# HSDACircuit.net
KiCad netlist of a schematic drawn in Altium Designer
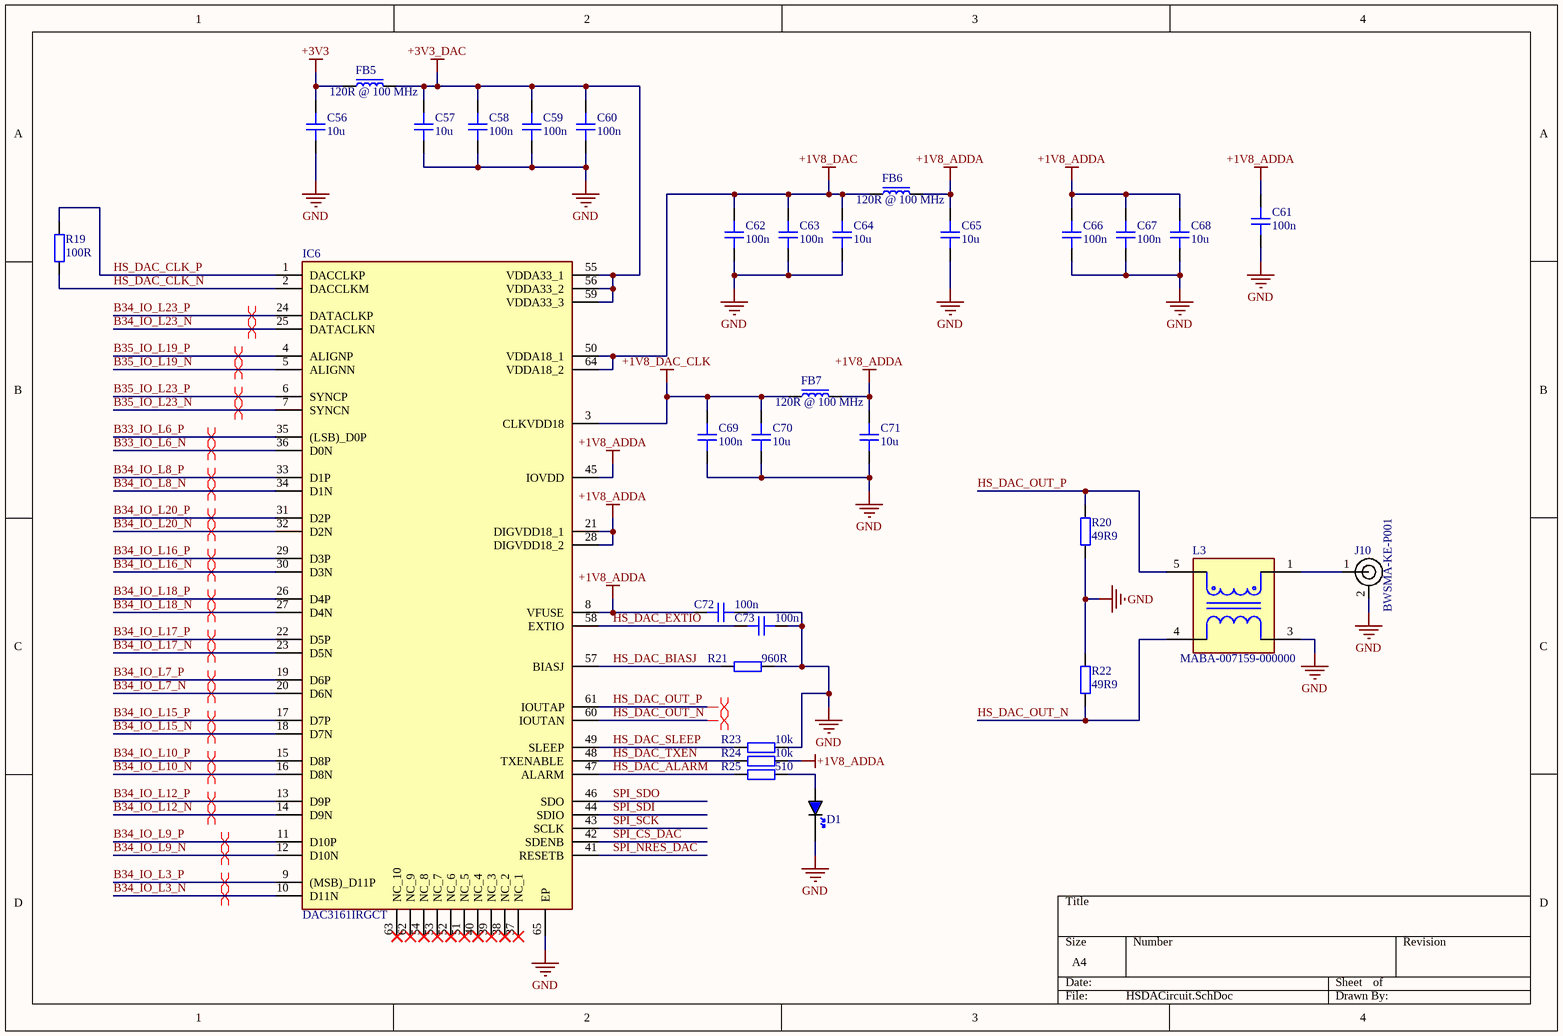
[diagram p0: HSDACircuit.SchDoc]

(export (version "E")
  (design (tool "Eeschema 10.0.6"))
  (components
    (comp (ref "C56")
      (value "10u")
      (footprint "CAP_0603")
      (description "Capacitor SMD 0603")
      (libsource (lib "Schematic-Lib-PhilsLab") (part "CAP_0603"))
    )
    (comp (ref "C57")
      (value "10u")
      (footprint "CAP_0603")
      (description "Capacitor SMD 0603")
      (libsource (lib "Schematic-Lib-PhilsLab") (part "CAP_0603"))
    )
    (comp (ref "C58")
      (value "100n")
      (footprint "CAP_0402")
      (description "Capacitor SMD 0402")
      (libsource (lib "Schematic-Lib-PhilsLab") (part "CAP_0402"))
    )
    (comp (ref "C59")
      (value "100n")
      (footprint "CAP_0402")
      (description "Capacitor SMD 0402")
      (libsource (lib "Schematic-Lib-PhilsLab") (part "CAP_0402"))
    )
    (comp (ref "C60")
      (value "100n")
      (footprint "CAP_0402")
      (description "Capacitor SMD 0402")
      (libsource (lib "Schematic-Lib-PhilsLab") (part "CAP_0402"))
    )
    (comp (ref "C61")
      (value "100n")
      (footprint "CAP_0402")
      (description "Capacitor SMD 0402")
      (libsource (lib "Schematic-Lib-PhilsLab") (part "CAP_0402"))
    )
    (comp (ref "C62")
      (value "100n")
      (footprint "CAP_0402")
      (description "Capacitor SMD 0402")
      (libsource (lib "Schematic-Lib-PhilsLab") (part "CAP_0402"))
    )
    (comp (ref "C63")
      (value "100n")
      (footprint "CAP_0402")
      (description "Capacitor SMD 0402")
      (libsource (lib "Schematic-Lib-PhilsLab") (part "CAP_0402"))
    )
    (comp (ref "C64")
      (value "10u")
      (footprint "CAP_0603")
      (description "Capacitor SMD 0603")
      (libsource (lib "Schematic-Lib-PhilsLab") (part "CAP_0603"))
    )
    (comp (ref "C65")
      (value "10u")
      (footprint "CAP_0603")
      (description "Capacitor SMD 0603")
      (libsource (lib "Schematic-Lib-PhilsLab") (part "CAP_0603"))
    )
    (comp (ref "C66")
      (value "100n")
      (footprint "CAP_0402")
      (description "Capacitor SMD 0402")
      (libsource (lib "Schematic-Lib-PhilsLab") (part "CAP_0402"))
    )
    (comp (ref "C67")
      (value "100n")
      (footprint "CAP_0402")
      (description "Capacitor SMD 0402")
      (libsource (lib "Schematic-Lib-PhilsLab") (part "CAP_0402"))
    )
    (comp (ref "C68")
      (value "10u")
      (footprint "CAP_0603")
      (description "Capacitor SMD 0603")
      (libsource (lib "Schematic-Lib-PhilsLab") (part "CAP_0603"))
    )
    (comp (ref "C69")
      (value "100n")
      (footprint "CAP_0402")
      (description "Capacitor SMD 0402")
      (libsource (lib "Schematic-Lib-PhilsLab") (part "CAP_0402"))
    )
    (comp (ref "C70")
      (value "10u")
      (footprint "CAP_0603")
      (description "Capacitor SMD 0603")
      (libsource (lib "Schematic-Lib-PhilsLab") (part "CAP_0603"))
    )
    (comp (ref "C71")
      (value "10u")
      (footprint "CAP_0603")
      (description "Capacitor SMD 0603")
      (libsource (lib "Schematic-Lib-PhilsLab") (part "CAP_0603"))
    )
    (comp (ref "C72")
      (value "100n")
      (footprint "CAP_0402")
      (description "Capacitor SMD 0402")
      (libsource (lib "Schematic-Lib-PhilsLab") (part "CAP_0402"))
    )
    (comp (ref "C73")
      (value "100n")
      (footprint "CAP_0402")
      (description "Capacitor SMD 0402")
      (libsource (lib "Schematic-Lib-PhilsLab") (part "CAP_0402"))
    )
    (comp (ref "D1")
      (value "BLUE")
      (footprint "LED_0603_BLUE")
      (description "LED 0603 BLUE SMD")
      (libsource (lib "Schematic-Lib-PhilsLab") (part "LED_0603_BLUE"))
    )
    (comp (ref "FB5")
      (value "120R @ 100 MHz")
      (footprint "FB_0603")
      (description "Ferrite Bead SMD 0603")
      (libsource (lib "") (part "FB_0603_1"))
    )
    (comp (ref "FB6")
      (value "120R @ 100 MHz")
      (footprint "FB_0603")
      (description "Ferrite Bead SMD 0603")
      (libsource (lib "Schematic-Lib-PhilsLab") (part "FB_0603"))
    )
    (comp (ref "FB7")
      (value "120R @ 100 MHz")
      (footprint "FB_0603")
      (description "Ferrite Bead SMD 0603")
      (libsource (lib "Schematic-Lib-PhilsLab") (part "FB_0603"))
    )
    (comp (ref "IC6")
      (value "DAC3161IRGCT")
      (footprint "JetsonTx2_PCBLib:QFN50P900X900X100-65N-D")
      (description "Integrated Circuit")
      (fields (field (name "MOUSER PART NUMBER") "595-DAC3161IRGCT"))
      (libsource (lib "JetsonTx2_SCHLib") (part "DAC3161IRGCT"))
    )
    (comp (ref "J10")
      (value "BWSMA-KE-P001")
      (footprint "BWSMA-KE-P001")
      (libsource (lib "JetsonTx2_SCHLib") (part "BWSMA-KE-P001"))
    )
    (comp (ref "L3")
      (value "MABA-007159-000000")
      (footprint "FP-MABA-007159-000000-MFG")
      (description "BALUN 4.5MHZ-3GHZ 1:1 6SMD FLAT")
      (libsource (lib "JetsonTx2_SCHLib") (part "MABA-007159-000000"))
    )
    (comp (ref "R19")
      (value "100R")
      (footprint "RES_0402")
      (description "Resistor SMD 0402")
      (libsource (lib "Schematic-Lib-PhilsLab") (part "RES_0402"))
    )
    (comp (ref "R20")
      (value "49R9")
      (footprint "RES_0402")
      (description "Resistor SMD 0402")
      (libsource (lib "Schematic-Lib-PhilsLab") (part "RES_0402"))
    )
    (comp (ref "R21")
      (value "960R")
      (footprint "RES_0402")
      (description "Resistor SMD 0402")
      (libsource (lib "Schematic-Lib-PhilsLab") (part "RES_0402"))
    )
    (comp (ref "R22")
      (value "49R9")
      (footprint "RES_0402")
      (description "Resistor SMD 0402")
      (libsource (lib "Schematic-Lib-PhilsLab") (part "RES_0402"))
    )
    (comp (ref "R23")
      (value "10k")
      (footprint "RES_0402")
      (description "Resistor SMD 0402")
      (libsource (lib "Schematic-Lib-PhilsLab") (part "RES_0402"))
    )
    (comp (ref "R24")
      (value "10k")
      (footprint "RES_0402")
      (description "Resistor SMD 0402")
      (libsource (lib "Schematic-Lib-PhilsLab") (part "RES_0402"))
    )
    (comp (ref "R25")
      (value "510")
      (footprint "RES_0603")
      (description "Resistor SMD 0603")
      (libsource (lib "Schematic-Lib-PhilsLab") (part "RES_0603"))
    )
  )
  (nets
    (net (code "1") (name "+1V8_ADDA") (class "Default")
      (node (ref "C61") (pin "1") (pinfunction "1_1") (pintype "passive"))
      (node (ref "C65") (pin "2") (pinfunction "2_2") (pintype "passive"))
      (node (ref "C66") (pin "1") (pinfunction "1_1") (pintype "passive"))
      (node (ref "C67") (pin "1") (pinfunction "1_1") (pintype "passive"))
      (node (ref "C68") (pin "2") (pinfunction "2_2") (pintype "passive"))
      (node (ref "C71") (pin "2") (pinfunction "2_2") (pintype "passive"))
      (node (ref "C72") (pin "1") (pinfunction "1_1") (pintype "passive"))
      (node (ref "FB6") (pin "2") (pinfunction "2_2") (pintype "passive"))
      (node (ref "FB7") (pin "2") (pinfunction "2_2") (pintype "passive"))
      (node (ref "IC6") (pin "21") (pinfunction "DIGVDD18_1_21") (pintype "passive"))
      (node (ref "IC6") (pin "28") (pinfunction "DIGVDD18_2_28") (pintype "passive"))
      (node (ref "IC6") (pin "45") (pinfunction "IOVDD_45") (pintype "passive"))
      (node (ref "IC6") (pin "8") (pinfunction "VFUSE_8") (pintype "passive"))
      (node (ref "R24") (pin "1") (pinfunction "1_1") (pintype "passive"))
    )
    (net (code "2") (name "+1V8_DAC") (class "Default")
      (node (ref "C62") (pin "1") (pinfunction "1_1") (pintype "passive"))
      (node (ref "C63") (pin "1") (pinfunction "1_1") (pintype "passive"))
      (node (ref "C64") (pin "2") (pinfunction "2_2") (pintype "passive"))
      (node (ref "FB6") (pin "1") (pinfunction "1_1") (pintype "passive"))
      (node (ref "IC6") (pin "50") (pinfunction "VDDA18_1_50") (pintype "passive"))
      (node (ref "IC6") (pin "64") (pinfunction "VDDA18_2_64") (pintype "passive"))
    )
    (net (code "3") (name "+1V8_DAC_CLK") (class "Default")
      (node (ref "C69") (pin "1") (pinfunction "1_1") (pintype "passive"))
      (node (ref "C70") (pin "2") (pinfunction "2_2") (pintype "passive"))
      (node (ref "FB7") (pin "1") (pinfunction "1_1") (pintype "passive"))
      (node (ref "IC6") (pin "3") (pinfunction "CLKVDD18_3") (pintype "passive"))
    )
    (net (code "4") (name "+3V3") (class "Default")
      (node (ref "C56") (pin "2") (pinfunction "2_2") (pintype "passive"))
      (node (ref "FB5") (pin "2") (pinfunction "2_2") (pintype "passive"))
    )
    (net (code "5") (name "+3V3_DAC") (class "Default")
      (node (ref "C57") (pin "2") (pinfunction "2_2") (pintype "passive"))
      (node (ref "C58") (pin "1") (pinfunction "1_1") (pintype "passive"))
      (node (ref "C59") (pin "1") (pinfunction "1_1") (pintype "passive"))
      (node (ref "C60") (pin "1") (pinfunction "1_1") (pintype "passive"))
      (node (ref "FB5") (pin "1") (pinfunction "1_1") (pintype "passive"))
      (node (ref "IC6") (pin "55") (pinfunction "VDDA33_1_55") (pintype "passive"))
      (node (ref "IC6") (pin "56") (pinfunction "VDDA33_2_56") (pintype "passive"))
      (node (ref "IC6") (pin "59") (pinfunction "VDDA33_3_59") (pintype "passive"))
    )
    (net (code "6") (name "/B33_IO_L6_N") (class "Default")
      (node (ref "IC6") (pin "36") (pinfunction "D0N_36") (pintype "passive"))
    )
    (net (code "7") (name "/B33_IO_L6_P") (class "Default")
      (node (ref "IC6") (pin "35") (pinfunction "(LSB)_D0P_35") (pintype "passive"))
    )
    (net (code "8") (name "/B34_IO_L3_N") (class "Default")
      (node (ref "IC6") (pin "10") (pinfunction "D11N_10") (pintype "passive"))
    )
    (net (code "9") (name "/B34_IO_L3_P") (class "Default")
      (node (ref "IC6") (pin "9") (pinfunction "(MSB)_D11P_9") (pintype "passive"))
    )
    (net (code "10") (name "/B34_IO_L7_N") (class "Default")
      (node (ref "IC6") (pin "20") (pinfunction "D6N_20") (pintype "passive"))
    )
    (net (code "11") (name "/B34_IO_L7_P") (class "Default")
      (node (ref "IC6") (pin "19") (pinfunction "D6P_19") (pintype "passive"))
    )
    (net (code "12") (name "/B34_IO_L8_N") (class "Default")
      (node (ref "IC6") (pin "34") (pinfunction "D1N_34") (pintype "passive"))
    )
    (net (code "13") (name "/B34_IO_L8_P") (class "Default")
      (node (ref "IC6") (pin "33") (pinfunction "D1P_33") (pintype "passive"))
    )
    (net (code "14") (name "/B34_IO_L9_N") (class "Default")
      (node (ref "IC6") (pin "12") (pinfunction "D10N_12") (pintype "passive"))
    )
    (net (code "15") (name "/B34_IO_L9_P") (class "Default")
      (node (ref "IC6") (pin "11") (pinfunction "D10P_11") (pintype "passive"))
    )
    (net (code "16") (name "/B34_IO_L10_N") (class "Default")
      (node (ref "IC6") (pin "16") (pinfunction "D8N_16") (pintype "passive"))
    )
    (net (code "17") (name "/B34_IO_L10_P") (class "Default")
      (node (ref "IC6") (pin "15") (pinfunction "D8P_15") (pintype "passive"))
    )
    (net (code "18") (name "/B34_IO_L12_N") (class "Default")
      (node (ref "IC6") (pin "14") (pinfunction "D9N_14") (pintype "passive"))
    )
    (net (code "19") (name "/B34_IO_L12_P") (class "Default")
      (node (ref "IC6") (pin "13") (pinfunction "D9P_13") (pintype "passive"))
    )
    (net (code "20") (name "/B34_IO_L15_N") (class "Default")
      (node (ref "IC6") (pin "18") (pinfunction "D7N_18") (pintype "passive"))
    )
    (net (code "21") (name "/B34_IO_L15_P") (class "Default")
      (node (ref "IC6") (pin "17") (pinfunction "D7P_17") (pintype "passive"))
    )
    (net (code "22") (name "/B34_IO_L16_N") (class "Default")
      (node (ref "IC6") (pin "30") (pinfunction "D3N_30") (pintype "passive"))
    )
    (net (code "23") (name "/B34_IO_L16_P") (class "Default")
      (node (ref "IC6") (pin "29") (pinfunction "D3P_29") (pintype "passive"))
    )
    (net (code "24") (name "/B34_IO_L17_N") (class "Default")
      (node (ref "IC6") (pin "23") (pinfunction "D5N_23") (pintype "passive"))
    )
    (net (code "25") (name "/B34_IO_L17_P") (class "Default")
      (node (ref "IC6") (pin "22") (pinfunction "D5P_22") (pintype "passive"))
    )
    (net (code "26") (name "/B34_IO_L18_N") (class "Default")
      (node (ref "IC6") (pin "27") (pinfunction "D4N_27") (pintype "passive"))
    )
    (net (code "27") (name "/B34_IO_L18_P") (class "Default")
      (node (ref "IC6") (pin "26") (pinfunction "D4P_26") (pintype "passive"))
    )
    (net (code "28") (name "/B34_IO_L20_N") (class "Default")
      (node (ref "IC6") (pin "32") (pinfunction "D2N_32") (pintype "passive"))
    )
    (net (code "29") (name "/B34_IO_L20_P") (class "Default")
      (node (ref "IC6") (pin "31") (pinfunction "D2P_31") (pintype "passive"))
    )
    (net (code "30") (name "/B34_IO_L23_N") (class "Default")
      (node (ref "IC6") (pin "25") (pinfunction "DATACLKN_25") (pintype "passive"))
    )
    (net (code "31") (name "/B34_IO_L23_P") (class "Default")
      (node (ref "IC6") (pin "24") (pinfunction "DATACLKP_24") (pintype "passive"))
    )
    (net (code "32") (name "/B35_IO_L19_N") (class "Default")
      (node (ref "IC6") (pin "5") (pinfunction "ALIGNN_5") (pintype "passive"))
    )
    (net (code "33") (name "/B35_IO_L19_P") (class "Default")
      (node (ref "IC6") (pin "4") (pinfunction "ALIGNP_4") (pintype "passive"))
    )
    (net (code "34") (name "/B35_IO_L23_N") (class "Default")
      (node (ref "IC6") (pin "7") (pinfunction "SYNCN_7") (pintype "passive"))
    )
    (net (code "35") (name "/B35_IO_L23_P") (class "Default")
      (node (ref "IC6") (pin "6") (pinfunction "SYNCP_6") (pintype "passive"))
    )
    (net (code "36") (name "/HS_DAC_ALARM") (class "Default")
      (node (ref "IC6") (pin "47") (pinfunction "ALARM_47") (pintype "passive"))
      (node (ref "R25") (pin "1") (pinfunction "1_1") (pintype "passive"))
    )
    (net (code "37") (name "/HS_DAC_BIASJ") (class "Default")
      (node (ref "IC6") (pin "57") (pinfunction "BIASJ_57") (pintype "passive"))
      (node (ref "R21") (pin "2") (pinfunction "2_2") (pintype "passive"))
    )
    (net (code "38") (name "/HS_DAC_CLK_N") (class "Default")
      (node (ref "IC6") (pin "2") (pinfunction "DACCLKM_2") (pintype "passive"))
      (node (ref "R19") (pin "1") (pinfunction "1_1") (pintype "passive"))
    )
    (net (code "39") (name "/HS_DAC_CLK_P") (class "Default")
      (node (ref "IC6") (pin "1") (pinfunction "DACCLKP_1") (pintype "passive"))
      (node (ref "R19") (pin "2") (pinfunction "2_2") (pintype "passive"))
    )
    (net (code "40") (name "/HS_DAC_EXTIO") (class "Default")
      (node (ref "C73") (pin "1") (pinfunction "1_1") (pintype "passive"))
      (node (ref "IC6") (pin "58") (pinfunction "EXTIO_58") (pintype "passive"))
    )
    (net (code "41") (name "/HS_DAC_OUT_N") (class "Default")
      (node (ref "IC6") (pin "60") (pinfunction "IOUTAN_60") (pintype "passive"))
      (node (ref "L3") (pin "4") (pinfunction "Primary_4") (pintype "passive"))
      (node (ref "R22") (pin "2") (pinfunction "2_2") (pintype "passive"))
    )
    (net (code "42") (name "/HS_DAC_OUT_P") (class "Default")
      (node (ref "IC6") (pin "61") (pinfunction "IOUTAP_61") (pintype "passive"))
      (node (ref "L3") (pin "5") (pinfunction "Primary_Dot_5") (pintype "passive"))
      (node (ref "R20") (pin "1") (pinfunction "1_1") (pintype "passive"))
    )
    (net (code "43") (name "/HS_DAC_SLEEP") (class "Default")
      (node (ref "IC6") (pin "49") (pinfunction "SLEEP_49") (pintype "passive"))
      (node (ref "R23") (pin "2") (pinfunction "2_2") (pintype "passive"))
    )
    (net (code "44") (name "/HS_DAC_TXEN") (class "Default")
      (node (ref "IC6") (pin "48") (pinfunction "TXENABLE_48") (pintype "passive"))
      (node (ref "R24") (pin "2") (pinfunction "2_2") (pintype "passive"))
    )
    (net (code "45") (name "/SPI_CS_DAC") (class "Default")
      (node (ref "IC6") (pin "42") (pinfunction "SDENB_42") (pintype "passive"))
    )
    (net (code "46") (name "/SPI_NRES_DAC") (class "Default")
      (node (ref "IC6") (pin "41") (pinfunction "RESETB_41") (pintype "passive"))
    )
    (net (code "47") (name "/SPI_SCK") (class "Default")
      (node (ref "IC6") (pin "43") (pinfunction "SCLK_43") (pintype "passive"))
    )
    (net (code "48") (name "/SPI_SDI") (class "Default")
      (node (ref "IC6") (pin "44") (pinfunction "SDIO_44") (pintype "passive"))
    )
    (net (code "49") (name "/SPI_SDO") (class "Default")
      (node (ref "IC6") (pin "46") (pinfunction "SDO_46") (pintype "passive"))
    )
    (net (code "50") (name "GND") (class "Default")
      (node (ref "C56") (pin "1") (pinfunction "1_1") (pintype "passive"))
      (node (ref "C57") (pin "1") (pinfunction "1_1") (pintype "passive"))
      (node (ref "C58") (pin "2") (pinfunction "2_2") (pintype "passive"))
      (node (ref "C59") (pin "2") (pinfunction "2_2") (pintype "passive"))
      (node (ref "C60") (pin "2") (pinfunction "2_2") (pintype "passive"))
      (node (ref "C61") (pin "2") (pinfunction "2_2") (pintype "passive"))
      (node (ref "C62") (pin "2") (pinfunction "2_2") (pintype "passive"))
      (node (ref "C63") (pin "2") (pinfunction "2_2") (pintype "passive"))
      (node (ref "C64") (pin "1") (pinfunction "1_1") (pintype "passive"))
      (node (ref "C65") (pin "1") (pinfunction "1_1") (pintype "passive"))
      (node (ref "C66") (pin "2") (pinfunction "2_2") (pintype "passive"))
      (node (ref "C67") (pin "2") (pinfunction "2_2") (pintype "passive"))
      (node (ref "C68") (pin "1") (pinfunction "1_1") (pintype "passive"))
      (node (ref "C69") (pin "2") (pinfunction "2_2") (pintype "passive"))
      (node (ref "C70") (pin "1") (pinfunction "1_1") (pintype "passive"))
      (node (ref "C71") (pin "1") (pinfunction "1_1") (pintype "passive"))
      (node (ref "C72") (pin "2") (pinfunction "2_2") (pintype "passive"))
      (node (ref "C73") (pin "2") (pinfunction "2_2") (pintype "passive"))
      (node (ref "D1") (pin "K") (pinfunction "K_K") (pintype "passive"))
      (node (ref "IC6") (pin "65") (pinfunction "EP_65") (pintype "passive"))
      (node (ref "J10") (pin "2") (pinfunction "2_2") (pintype "passive"))
      (node (ref "L3") (pin "3") (pinfunction "Secondary_3") (pintype "passive"))
      (node (ref "R20") (pin "2") (pinfunction "2_2") (pintype "passive"))
      (node (ref "R21") (pin "1") (pinfunction "1_1") (pintype "passive"))
      (node (ref "R22") (pin "1") (pinfunction "1_1") (pintype "passive"))
      (node (ref "R23") (pin "1") (pinfunction "1_1") (pintype "passive"))
    )
    (net (code "51") (name "Net-(D1-PadA)") (class "Default")
      (node (ref "D1") (pin "A") (pinfunction "A_A") (pintype "passive"))
      (node (ref "R25") (pin "2") (pinfunction "2_2") (pintype "passive"))
    )
    (net (code "52") (name "Net-(L3-Secondary_Dot)") (class "Default")
      (node (ref "J10") (pin "1") (pinfunction "1_1") (pintype "passive"))
      (node (ref "L3") (pin "1") (pinfunction "Secondary_Dot_1") (pintype "passive"))
    )
    (net (code "53") (name "unconnected-(IC6-NC_1-Pad37)") (class "Default")
      (node (ref "IC6") (pin "37") (pinfunction "NC_1_37") (pintype "passive+no_connect"))
    )
    (net (code "54") (name "unconnected-(IC6-NC_2-Pad38)") (class "Default")
      (node (ref "IC6") (pin "38") (pinfunction "NC_2_38") (pintype "passive+no_connect"))
    )
    (net (code "55") (name "unconnected-(IC6-NC_3-Pad39)") (class "Default")
      (node (ref "IC6") (pin "39") (pinfunction "NC_3_39") (pintype "passive+no_connect"))
    )
    (net (code "56") (name "unconnected-(IC6-NC_4-Pad40)") (class "Default")
      (node (ref "IC6") (pin "40") (pinfunction "NC_4_40") (pintype "passive+no_connect"))
    )
    (net (code "57") (name "unconnected-(IC6-NC_5-Pad51)") (class "Default")
      (node (ref "IC6") (pin "51") (pinfunction "NC_5_51") (pintype "passive+no_connect"))
    )
    (net (code "58") (name "unconnected-(IC6-NC_6-Pad52)") (class "Default")
      (node (ref "IC6") (pin "52") (pinfunction "NC_6_52") (pintype "passive+no_connect"))
    )
    (net (code "59") (name "unconnected-(IC6-NC_7-Pad53)") (class "Default")
      (node (ref "IC6") (pin "53") (pinfunction "NC_7_53") (pintype "passive+no_connect"))
    )
    (net (code "60") (name "unconnected-(IC6-NC_8-Pad54)") (class "Default")
      (node (ref "IC6") (pin "54") (pinfunction "NC_8_54") (pintype "passive+no_connect"))
    )
    (net (code "61") (name "unconnected-(IC6-NC_9-Pad62)") (class "Default")
      (node (ref "IC6") (pin "62") (pinfunction "NC_9_62") (pintype "passive+no_connect"))
    )
    (net (code "62") (name "unconnected-(IC6-NC_10-Pad63)") (class "Default")
      (node (ref "IC6") (pin "63") (pinfunction "NC_10_63") (pintype "passive+no_connect"))
    )
  )
)
